# muC.net
KiCad netlist of a schematic drawn in Altium Designer
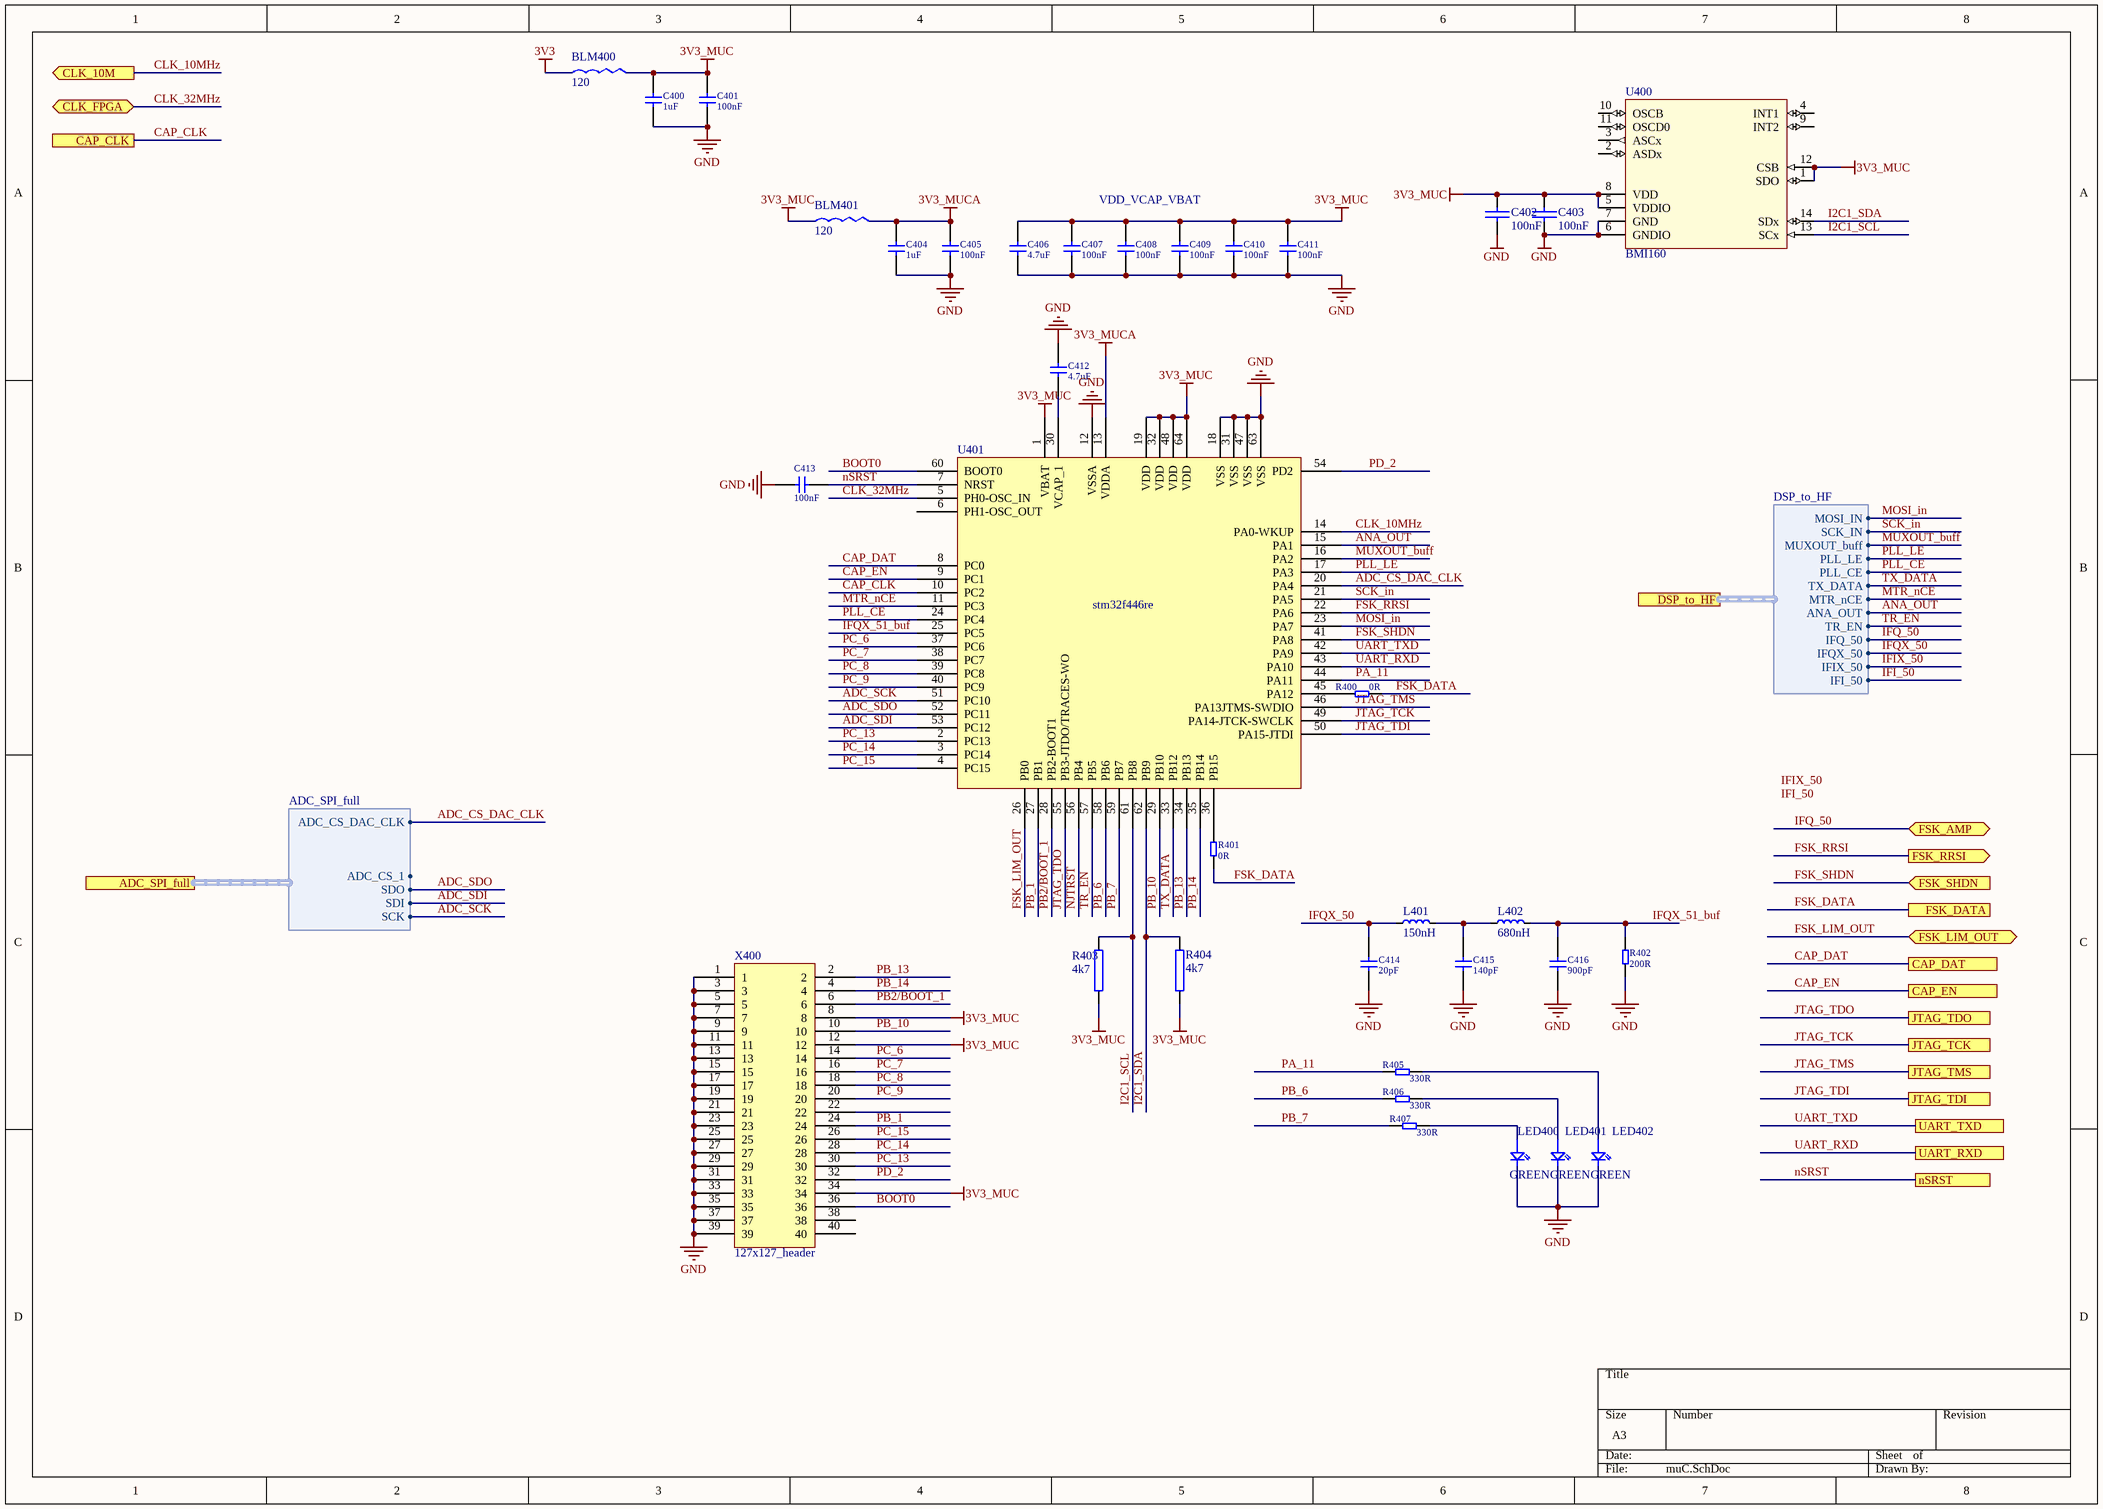
[diagram p0: muC.SchDoc]

(export (version "E")
  (design (tool "Eeschema 10.0.6"))
  (components
    (comp (ref "BLM400")
      (value "FerriteBeat")
      (footprint "BLM18SG121TN1")
      (description "BLM18SG121TN1")
      (fields (field (name "ALTIUM_UNNAMED_1") "120"))
      (libsource (lib "zynq_board") (part "FerriteBeat"))
    )
    (comp (ref "BLM401")
      (value "FerriteBeat")
      (footprint "BLM18SG121TN1")
      (description "BLM18SG121TN1")
      (fields (field (name "ALTIUM_UNNAMED_1") "120"))
      (libsource (lib "zynq_board") (part "FerriteBeat"))
    )
    (comp (ref "C400")
      (value "1uF")
      (footprint "C_SMD_0603")
      (description "1uF, 0603, 6.3V, 10%, X5R")
      (fields (field (name "Comment") "SMD capacitor"))
      (libsource (lib "zynq_board") (part "C_SMD"))
    )
    (comp (ref "C401")
      (value "100nF")
      (footprint "C_SMD_0402")
      (description "100nF, 0402, 6.3V, 10%, X5R")
      (fields (field (name "Comment") "SMD capacitor"))
      (libsource (lib "zynq_board") (part "C_SMD"))
    )
    (comp (ref "C402")
      (value "100nF")
      (footprint "0402RN")
      (description "MLCC, X7R, 16V, 5%, 0402")
      (fields (field (name "PART NUMBER") "100n, 0402, 16V, X7R, 5%"))
      (libsource (lib "Symeo_libs") (part "_CAP"))
    )
    (comp (ref "C403")
      (value "100nF")
      (footprint "0402RN")
      (description "MLCC, X7R, 16V, 5%, 0402")
      (fields (field (name "PART NUMBER") "100n, 0402, 16V, X7R, 5%"))
      (libsource (lib "Symeo_libs") (part "_CAP"))
    )
    (comp (ref "C404")
      (value "1uF")
      (footprint "C_SMD_0603")
      (description "1uF, 0603, 6.3V, 10%, X5R")
      (fields (field (name "Comment") "SMD capacitor"))
      (libsource (lib "zynq_board") (part "C_SMD"))
    )
    (comp (ref "C405")
      (value "100nF")
      (footprint "C_SMD_0402")
      (description "100nF, 0402, 6.3V, 10%, X5R")
      (fields (field (name "Comment") "SMD capacitor"))
      (libsource (lib "zynq_board") (part "C_SMD"))
    )
    (comp (ref "C406")
      (value "4.7uF")
      (footprint "C_SMD_0603")
      (description "4.7uF, 0603, 6.3V, 10%, X5R")
      (fields (field (name "Comment") "SMD capacitor"))
      (libsource (lib "zynq_board") (part "C_SMD"))
    )
    (comp (ref "C407")
      (value "100nF")
      (footprint "C_SMD_0402")
      (description "100nF, 0402, 6.3V, 10%, X5R")
      (fields (field (name "Comment") "SMD capacitor"))
      (libsource (lib "zynq_board") (part "C_SMD"))
    )
    (comp (ref "C408")
      (value "100nF")
      (footprint "C_SMD_0402")
      (description "100nF, 0402, 6.3V, 10%, X5R")
      (fields (field (name "Comment") "SMD capacitor"))
      (libsource (lib "zynq_board") (part "C_SMD"))
    )
    (comp (ref "C409")
      (value "100nF")
      (footprint "C_SMD_0402")
      (description "100nF, 0402, 6.3V, 10%, X5R")
      (fields (field (name "Comment") "SMD capacitor"))
      (libsource (lib "zynq_board") (part "C_SMD"))
    )
    (comp (ref "C410")
      (value "100nF")
      (footprint "C_SMD_0402")
      (description "100nF, 0402, 6.3V, 10%, X5R")
      (fields (field (name "Comment") "SMD capacitor"))
      (libsource (lib "zynq_board") (part "C_SMD"))
    )
    (comp (ref "C411")
      (value "100nF")
      (footprint "C_SMD_0402")
      (description "100nF, 0402, 6.3V, 10%, X5R")
      (fields (field (name "Comment") "SMD capacitor"))
      (libsource (lib "zynq_board") (part "C_SMD"))
    )
    (comp (ref "C412")
      (value "4.7uF")
      (footprint "C_SMD_0603")
      (description "4.7uF, 0603, 6.3V, 10%, X5R")
      (fields (field (name "Comment") "SMD capacitor"))
      (libsource (lib "zynq_board") (part "C_SMD"))
    )
    (comp (ref "C413")
      (value "100nF")
      (footprint "C_SMD_0402")
      (description "100nF, 0402, 6.3V, 10%, X5R")
      (fields (field (name "Comment") "SMD capacitor"))
      (libsource (lib "zynq_board") (part "C_SMD"))
    )
    (comp (ref "C414")
      (value "20pF")
      (footprint "C_SMD_0402")
      (description "20pF, 0402, 6.3V, 10%, X5R")
      (fields (field (name "Comment") "SMD capacitor"))
      (libsource (lib "zynq_board") (part "C_SMD"))
    )
    (comp (ref "C415")
      (value "140pF")
      (footprint "C_SMD_0402")
      (description "140pF, 0402, 6.3V, 10%, X5R")
      (fields (field (name "Comment") "SMD capacitor"))
      (libsource (lib "zynq_board") (part "C_SMD"))
    )
    (comp (ref "C416")
      (value "900pF")
      (footprint "C_SMD_0402")
      (description "900pF, 0402, 6.3V, 10%, X5R")
      (fields (field (name "Comment") "SMD capacitor"))
      (libsource (lib "zynq_board") (part "C_SMD"))
    )
    (comp (ref "L401")
      (value "150nH")
      (footprint "L_0805")
      (description "744761215A,150nH Inductor, Würth Elektorn")
      (libsource (lib "zynq_board") (part "744761215A"))
    )
    (comp (ref "L402")
      (value "680nH")
      (footprint "L_0805")
      (description "744761268A, 680nH")
      (libsource (lib "zynq_board") (part "744761268A"))
    )
    (comp (ref "LED400")
      (value "KPHHS-1005")
      (footprint "R_SMD_0402")
      (fields (field (name "ALTIUM_UNNAMED_1") "GREEN"))
      (libsource (lib "zynq_board") (part "KPHHS-1005"))
    )
    (comp (ref "LED401")
      (value "KPHHS-1005")
      (footprint "R_SMD_0402")
      (fields (field (name "ALTIUM_UNNAMED_1") "GREEN"))
      (libsource (lib "zynq_board") (part "KPHHS-1005"))
    )
    (comp (ref "LED402")
      (value "KPHHS-1005")
      (footprint "R_SMD_0402")
      (fields (field (name "ALTIUM_UNNAMED_1") "GREEN"))
      (libsource (lib "zynq_board") (part "KPHHS-1005"))
    )
    (comp (ref "R400")
      (value "0R")
      (footprint "R_SMD_0402")
      (description "0R,0402")
      (fields (field (name "Comment") "SMD Resistor"))
      (libsource (lib "zynq_board") (part "R_SMD"))
    )
    (comp (ref "R401")
      (value "0R")
      (footprint "R_SMD_0402")
      (description "0R,0402")
      (fields (field (name "Comment") "SMD Resistor"))
      (libsource (lib "zynq_board") (part "R_SMD"))
    )
    (comp (ref "R402")
      (value "200R")
      (footprint "R_SMD_0402")
      (description "200R, 0402, 1%")
      (fields (field (name "Comment") "SMD Resistor"))
      (libsource (lib "zynq_board") (part "R_SMD"))
    )
    (comp (ref "R403")
      (value "4k7")
      (footprint "0402RN")
      (description "1%, 0.063W, 50V, 0402")
      (fields (field (name "PART NUMBER") "4k7, 0402, 1%, 0.063W, 50V"))
      (libsource (lib "Symeo_libs") (part "_RES"))
    )
    (comp (ref "R404")
      (value "4k7")
      (footprint "0402RN")
      (description "1%, 0.063W, 50V, 0402")
      (fields (field (name "PART NUMBER") "4k7, 0402, 1%, 0.063W, 50V"))
      (libsource (lib "Symeo_libs") (part "_RES"))
    )
    (comp (ref "R405")
      (value "330R")
      (footprint "R_SMD_0402")
      (description "330R, 0402, 1%")
      (fields (field (name "Comment") "SMD Resistor"))
      (libsource (lib "zynq_board") (part "R_SMD"))
    )
    (comp (ref "R406")
      (value "330R")
      (footprint "R_SMD_0402")
      (description "330R, 0402, 1%")
      (fields (field (name "Comment") "SMD Resistor"))
      (libsource (lib "zynq_board") (part "R_SMD"))
    )
    (comp (ref "R407")
      (value "330R")
      (footprint "R_SMD_0402")
      (description "330R, 0402, 1%")
      (fields (field (name "Comment") "SMD Resistor"))
      (libsource (lib "zynq_board") (part "R_SMD"))
    )
    (comp (ref "U400")
      (value "BMI160")
      (footprint "BMI160")
      (description "Bosch Accelerometer and Gyro; I2C & SPI")
      (fields (field (name "PART NUMBER") "Sensor BMI160"))
      (libsource (lib "Symeo_libs") (part "BMI160"))
    )
    (comp (ref "U401")
      (value "stm32f446re")
      (footprint "LQFP64")
      (description "32uC")
      (libsource (lib "zynq_board") (part "stm32f446re"))
    )
    (comp (ref "X400")
      (value "127x127_header")
      (footprint "Header_127x127_40PIN")
      (description "127x127_header_throughole, 2x20")
      (libsource (lib "zynq_board") (part "Header_2x20_127mm"))
    )
  )
  (nets
    (net (code "3") (name "/ADC_CS_DAC_CLK") (class "Default")
      (node (ref "U401") (pin "20") (pinfunction "PA4_20") (pintype "passive"))
    )
    (net (code "4") (name "/ADC_SCK") (class "Default")
      (node (ref "U401") (pin "51") (pinfunction "PC10_51") (pintype "passive"))
    )
    (net (code "5") (name "/ADC_SDI") (class "Default")
      (node (ref "U401") (pin "53") (pinfunction "PC12_53") (pintype "passive"))
    )
    (net (code "6") (name "/ADC_SDO") (class "Default")
      (node (ref "U401") (pin "52") (pinfunction "PC11_52") (pintype "passive"))
    )
    (net (code "7") (name "/ANA_OUT") (class "Default")
      (node (ref "U401") (pin "15") (pinfunction "PA1_15") (pintype "passive"))
    )
    (net (code "8") (name "/BOOT0") (class "Default")
      (node (ref "U401") (pin "60") (pinfunction "BOOT0_60") (pintype "passive"))
      (node (ref "X400") (pin "36") (pinfunction "36_36") (pintype "passive"))
    )
    (net (code "9") (name "/CAP_CLK") (class "Default")
      (node (ref "U401") (pin "10") (pinfunction "PC2_10") (pintype "passive"))
    )
    (net (code "10") (name "/CAP_DAT") (class "Default")
      (node (ref "U401") (pin "8") (pinfunction "PC0_8") (pintype "passive"))
    )
    (net (code "11") (name "/CAP_EN") (class "Default")
      (node (ref "U401") (pin "9") (pinfunction "PC1_9") (pintype "passive"))
    )
    (net (code "12") (name "/CLK_10MHz") (class "Default")
      (node (ref "U401") (pin "14") (pinfunction "PA0-WKUP_14") (pintype "passive"))
    )
    (net (code "13") (name "/CLK_32MHz") (class "Default")
      (node (ref "U401") (pin "5") (pinfunction "PH0-OSC_IN_5") (pintype "passive"))
    )
    (net (code "14") (name "/FSK_DATA") (class "Default")
      (node (ref "R400") (pin "1") (pinfunction "1_1") (pintype "passive"))
      (node (ref "R401") (pin "2") (pinfunction "2_2") (pintype "passive"))
    )
    (net (code "15") (name "/FSK_LIM_OUT") (class "Default")
      (node (ref "U401") (pin "26") (pinfunction "PB0_26") (pintype "passive"))
    )
    (net (code "16") (name "/FSK_RRSI") (class "Default")
      (node (ref "U401") (pin "22") (pinfunction "PA6_22") (pintype "passive"))
    )
    (net (code "17") (name "/FSK_SHDN") (class "Default")
      (node (ref "U401") (pin "41") (pinfunction "PA8_41") (pintype "passive"))
    )
    (net (code "18") (name "/I2C1_SCL") (class "Default")
      (node (ref "R403") (pin "2") (pintype "passive"))
      (node (ref "U400") (pin "13") (pinfunction "SCx_13") (pintype "input"))
      (node (ref "U401") (pin "61") (pinfunction "PB8_61") (pintype "passive"))
    )
    (net (code "19") (name "/I2C1_SDA") (class "Default")
      (node (ref "R404") (pin "2") (pintype "passive"))
      (node (ref "U400") (pin "14") (pinfunction "SDx_14") (pintype "bidirectional"))
      (node (ref "U401") (pin "62") (pinfunction "PB9_62") (pintype "passive"))
    )
    (net (code "22") (name "/IFQX_50") (class "Default")
      (node (ref "C414") (pin "1") (pinfunction "1_1") (pintype "passive"))
      (node (ref "L401") (pin "2") (pinfunction "2_2") (pintype "passive"))
    )
    (net (code "23") (name "/IFQX_51_buf") (class "Default")
      (node (ref "C416") (pin "1") (pinfunction "1_1") (pintype "passive"))
      (node (ref "L402") (pin "1") (pinfunction "1_1") (pintype "passive"))
      (node (ref "R402") (pin "1") (pinfunction "1_1") (pintype "passive"))
      (node (ref "U401") (pin "25") (pinfunction "PC5_25") (pintype "passive"))
    )
    (net (code "25") (name "/JTAG_TCK") (class "Default")
      (node (ref "U401") (pin "49") (pinfunction "PA14-JTCK-SWCLK_49") (pintype "passive"))
    )
    (net (code "26") (name "/JTAG_TDI") (class "Default")
      (node (ref "U401") (pin "50") (pinfunction "PA15-JTDI_50") (pintype "passive"))
    )
    (net (code "27") (name "/JTAG_TDO") (class "Default")
      (node (ref "U401") (pin "55") (pinfunction "PB3-JTDO/TRACES-WO_55") (pintype "passive"))
    )
    (net (code "28") (name "/JTAG_TMS") (class "Default")
      (node (ref "U401") (pin "46") (pinfunction "PA13JTMS-SWDIO_46") (pintype "passive"))
    )
    (net (code "29") (name "/MOSI_in") (class "Default")
      (node (ref "U401") (pin "23") (pinfunction "PA7_23") (pintype "passive"))
    )
    (net (code "30") (name "/MTR_nCE") (class "Default")
      (node (ref "U401") (pin "11") (pinfunction "PC3_11") (pintype "passive"))
    )
    (net (code "31") (name "/MUXOUT_buff") (class "Default")
      (node (ref "U401") (pin "16") (pinfunction "PA2_16") (pintype "passive"))
    )
    (net (code "32") (name "/NJTRST") (class "Default")
      (node (ref "U401") (pin "56") (pinfunction "PB4_56") (pintype "passive"))
    )
    (net (code "33") (name "/PA_11") (class "Default")
      (node (ref "R405") (pin "1") (pinfunction "1_1") (pintype "passive"))
      (node (ref "U401") (pin "44") (pinfunction "PA11_44") (pintype "passive"))
    )
    (net (code "34") (name "/PB2{slash}BOOT_1") (class "Default")
      (node (ref "U401") (pin "28") (pinfunction "PB2-BOOT1_28") (pintype "passive"))
      (node (ref "X400") (pin "6") (pinfunction "6_6") (pintype "passive"))
    )
    (net (code "35") (name "/PB_1") (class "Default")
      (node (ref "U401") (pin "27") (pinfunction "PB1_27") (pintype "passive"))
      (node (ref "X400") (pin "24") (pinfunction "24_24") (pintype "passive"))
    )
    (net (code "36") (name "/PB_6") (class "Default")
      (node (ref "R406") (pin "1") (pinfunction "1_1") (pintype "passive"))
      (node (ref "U401") (pin "58") (pinfunction "PB6_58") (pintype "passive"))
    )
    (net (code "37") (name "/PB_7") (class "Default")
      (node (ref "R407") (pin "1") (pinfunction "1_1") (pintype "passive"))
      (node (ref "U401") (pin "59") (pinfunction "PB7_59") (pintype "passive"))
    )
    (net (code "38") (name "/PB_10") (class "Default")
      (node (ref "U401") (pin "29") (pinfunction "PB10_29") (pintype "passive"))
      (node (ref "X400") (pin "10") (pinfunction "10_10") (pintype "passive"))
    )
    (net (code "39") (name "/PB_13") (class "Default")
      (node (ref "U401") (pin "34") (pinfunction "PB13_34") (pintype "passive"))
      (node (ref "X400") (pin "2") (pinfunction "2_2") (pintype "passive"))
    )
    (net (code "40") (name "/PB_14") (class "Default")
      (node (ref "U401") (pin "35") (pinfunction "PB14_35") (pintype "passive"))
      (node (ref "X400") (pin "4") (pinfunction "4_4") (pintype "passive"))
    )
    (net (code "41") (name "/PC_6") (class "Default")
      (node (ref "U401") (pin "37") (pinfunction "PC6_37") (pintype "passive"))
      (node (ref "X400") (pin "14") (pinfunction "14_14") (pintype "passive"))
    )
    (net (code "42") (name "/PC_7") (class "Default")
      (node (ref "U401") (pin "38") (pinfunction "PC7_38") (pintype "passive"))
      (node (ref "X400") (pin "16") (pinfunction "16_16") (pintype "passive"))
    )
    (net (code "43") (name "/PC_8") (class "Default")
      (node (ref "U401") (pin "39") (pinfunction "PC8_39") (pintype "passive"))
      (node (ref "X400") (pin "18") (pinfunction "18_18") (pintype "passive"))
    )
    (net (code "44") (name "/PC_9") (class "Default")
      (node (ref "U401") (pin "40") (pinfunction "PC9_40") (pintype "passive"))
      (node (ref "X400") (pin "20") (pinfunction "20_20") (pintype "passive"))
    )
    (net (code "45") (name "/PC_13") (class "Default")
      (node (ref "U401") (pin "2") (pinfunction "PC13_2") (pintype "passive"))
      (node (ref "X400") (pin "30") (pinfunction "30_30") (pintype "passive"))
    )
    (net (code "46") (name "/PC_14") (class "Default")
      (node (ref "U401") (pin "3") (pinfunction "PC14_3") (pintype "passive"))
      (node (ref "X400") (pin "28") (pinfunction "28_28") (pintype "passive"))
    )
    (net (code "47") (name "/PC_15") (class "Default")
      (node (ref "U401") (pin "4") (pinfunction "PC15_4") (pintype "passive"))
      (node (ref "X400") (pin "26") (pinfunction "26_26") (pintype "passive"))
    )
    (net (code "48") (name "/PD_2") (class "Default")
      (node (ref "U401") (pin "54") (pinfunction "PD2_54") (pintype "passive"))
      (node (ref "X400") (pin "32") (pinfunction "32_32") (pintype "passive"))
    )
    (net (code "49") (name "/PLL_CE") (class "Default")
      (node (ref "U401") (pin "24") (pinfunction "PC4_24") (pintype "passive"))
    )
    (net (code "50") (name "/PLL_LE") (class "Default")
      (node (ref "U401") (pin "17") (pinfunction "PA3_17") (pintype "passive"))
    )
    (net (code "51") (name "/SCK_in") (class "Default")
      (node (ref "U401") (pin "21") (pinfunction "PA5_21") (pintype "passive"))
    )
    (net (code "52") (name "/TR_EN") (class "Default")
      (node (ref "U401") (pin "57") (pinfunction "PB5_57") (pintype "passive"))
    )
    (net (code "53") (name "/TX_DATA") (class "Default")
      (node (ref "U401") (pin "33") (pinfunction "PB12_33") (pintype "passive"))
    )
    (net (code "54") (name "/UART_RXD") (class "Default")
      (node (ref "U401") (pin "43") (pinfunction "PA10_43") (pintype "passive"))
    )
    (net (code "55") (name "/UART_TXD") (class "Default")
      (node (ref "U401") (pin "42") (pinfunction "PA9_42") (pintype "passive"))
    )
    (net (code "56") (name "/nSRST") (class "Default")
      (node (ref "C413") (pin "1") (pinfunction "1_1") (pintype "passive"))
      (node (ref "U401") (pin "7") (pinfunction "NRST_7") (pintype "passive"))
    )
    (net (code "59") (name "3V3") (class "Default")
      (node (ref "BLM400") (pin "1") (pinfunction "1_1") (pintype "passive"))
    )
    (net (code "60") (name "3V3_MUC") (class "Default")
      (node (ref "BLM400") (pin "2") (pinfunction "2_2") (pintype "passive"))
      (node (ref "BLM401") (pin "1") (pinfunction "1_1") (pintype "passive"))
      (node (ref "C400") (pin "1") (pinfunction "1_1") (pintype "passive"))
      (node (ref "C401") (pin "1") (pinfunction "1_1") (pintype "passive"))
      (node (ref "C402") (pin "1") (pintype "passive"))
      (node (ref "C403") (pin "1") (pintype "passive"))
      (node (ref "C406") (pin "1") (pinfunction "1_1") (pintype "passive"))
      (node (ref "C407") (pin "1") (pinfunction "1_1") (pintype "passive"))
      (node (ref "C408") (pin "1") (pinfunction "1_1") (pintype "passive"))
      (node (ref "C409") (pin "1") (pinfunction "1_1") (pintype "passive"))
      (node (ref "C410") (pin "1") (pinfunction "1_1") (pintype "passive"))
      (node (ref "C411") (pin "1") (pinfunction "1_1") (pintype "passive"))
      (node (ref "R403") (pin "1") (pintype "passive"))
      (node (ref "R404") (pin "1") (pintype "passive"))
      (node (ref "U400") (pin "1") (pinfunction "SDO_1") (pintype "bidirectional"))
      (node (ref "U400") (pin "12") (pinfunction "CSB_12") (pintype "input"))
      (node (ref "U400") (pin "5") (pinfunction "VDDIO_5") (pintype "power_in"))
      (node (ref "U400") (pin "8") (pinfunction "VDD_8") (pintype "power_in"))
      (node (ref "U401") (pin "1") (pinfunction "VBAT_1") (pintype "passive"))
      (node (ref "U401") (pin "19") (pinfunction "VDD_19") (pintype "passive"))
      (node (ref "U401") (pin "32") (pinfunction "VDD_32") (pintype "passive"))
      (node (ref "U401") (pin "48") (pinfunction "VDD_48") (pintype "passive"))
      (node (ref "U401") (pin "64") (pinfunction "VDD_64") (pintype "passive"))
      (node (ref "X400") (pin "12") (pinfunction "12_12") (pintype "passive"))
      (node (ref "X400") (pin "34") (pinfunction "34_34") (pintype "passive"))
      (node (ref "X400") (pin "8") (pinfunction "8_8") (pintype "passive"))
    )
    (net (code "61") (name "3V3_MUCA") (class "Default")
      (node (ref "BLM401") (pin "2") (pinfunction "2_2") (pintype "passive"))
      (node (ref "C404") (pin "1") (pinfunction "1_1") (pintype "passive"))
      (node (ref "C405") (pin "1") (pinfunction "1_1") (pintype "passive"))
      (node (ref "U401") (pin "13") (pinfunction "VDDA_13") (pintype "passive"))
    )
    (net (code "62") (name "GND") (class "Default")
      (node (ref "C400") (pin "2") (pinfunction "2_2") (pintype "passive"))
      (node (ref "C401") (pin "2") (pinfunction "2_2") (pintype "passive"))
      (node (ref "C402") (pin "2") (pintype "passive"))
      (node (ref "C403") (pin "2") (pintype "passive"))
      (node (ref "C404") (pin "2") (pinfunction "2_2") (pintype "passive"))
      (node (ref "C405") (pin "2") (pinfunction "2_2") (pintype "passive"))
      (node (ref "C406") (pin "2") (pinfunction "2_2") (pintype "passive"))
      (node (ref "C407") (pin "2") (pinfunction "2_2") (pintype "passive"))
      (node (ref "C408") (pin "2") (pinfunction "2_2") (pintype "passive"))
      (node (ref "C409") (pin "2") (pinfunction "2_2") (pintype "passive"))
      (node (ref "C410") (pin "2") (pinfunction "2_2") (pintype "passive"))
      (node (ref "C411") (pin "2") (pinfunction "2_2") (pintype "passive"))
      (node (ref "C412") (pin "2") (pinfunction "2_2") (pintype "passive"))
      (node (ref "C413") (pin "2") (pinfunction "2_2") (pintype "passive"))
      (node (ref "C414") (pin "2") (pinfunction "2_2") (pintype "passive"))
      (node (ref "C415") (pin "2") (pinfunction "2_2") (pintype "passive"))
      (node (ref "C416") (pin "2") (pinfunction "2_2") (pintype "passive"))
      (node (ref "LED400") (pin "2") (pinfunction "2_2") (pintype "passive"))
      (node (ref "LED401") (pin "2") (pinfunction "2_2") (pintype "passive"))
      (node (ref "LED402") (pin "2") (pinfunction "2_2") (pintype "passive"))
      (node (ref "R402") (pin "2") (pinfunction "2_2") (pintype "passive"))
      (node (ref "U400") (pin "6") (pinfunction "GNDIO_6") (pintype "power_in"))
      (node (ref "U400") (pin "7") (pinfunction "GND_7") (pintype "power_in"))
      (node (ref "U401") (pin "12") (pinfunction "VSSA_12") (pintype "passive"))
      (node (ref "U401") (pin "18") (pinfunction "VSS_18") (pintype "passive"))
      (node (ref "U401") (pin "31") (pinfunction "VSS_31") (pintype "passive"))
      (node (ref "U401") (pin "47") (pinfunction "VSS_47") (pintype "passive"))
      (node (ref "U401") (pin "63") (pinfunction "VSS_63") (pintype "passive"))
      (node (ref "X400") (pin "1") (pinfunction "1_1") (pintype "passive"))
      (node (ref "X400") (pin "11") (pinfunction "11_11") (pintype "passive"))
      (node (ref "X400") (pin "13") (pinfunction "13_13") (pintype "passive"))
      (node (ref "X400") (pin "15") (pinfunction "15_15") (pintype "passive"))
      (node (ref "X400") (pin "17") (pinfunction "17_17") (pintype "passive"))
      (node (ref "X400") (pin "19") (pinfunction "19_19") (pintype "passive"))
      (node (ref "X400") (pin "21") (pinfunction "21_21") (pintype "passive"))
      (node (ref "X400") (pin "23") (pinfunction "23_23") (pintype "passive"))
      (node (ref "X400") (pin "25") (pinfunction "25_25") (pintype "passive"))
      (node (ref "X400") (pin "27") (pinfunction "27_27") (pintype "passive"))
      (node (ref "X400") (pin "29") (pinfunction "29_29") (pintype "passive"))
      (node (ref "X400") (pin "3") (pinfunction "3_3") (pintype "passive"))
      (node (ref "X400") (pin "31") (pinfunction "31_31") (pintype "passive"))
      (node (ref "X400") (pin "33") (pinfunction "33_33") (pintype "passive"))
      (node (ref "X400") (pin "35") (pinfunction "35_35") (pintype "passive"))
      (node (ref "X400") (pin "37") (pinfunction "37_37") (pintype "passive"))
      (node (ref "X400") (pin "39") (pinfunction "39_39") (pintype "passive"))
      (node (ref "X400") (pin "5") (pinfunction "5_5") (pintype "passive"))
      (node (ref "X400") (pin "7") (pinfunction "7_7") (pintype "passive"))
      (node (ref "X400") (pin "9") (pinfunction "9_9") (pintype "passive"))
    )
    (net (code "63") (name "Net-(C415-Pad1)") (class "Default")
      (node (ref "C415") (pin "1") (pinfunction "1_1") (pintype "passive"))
      (node (ref "L401") (pin "1") (pinfunction "1_1") (pintype "passive"))
      (node (ref "L402") (pin "2") (pinfunction "2_2") (pintype "passive"))
    )
    (net (code "64") (name "Net-(LED400-Pad1)") (class "Default")
      (node (ref "LED400") (pin "1") (pinfunction "1_1") (pintype "passive"))
      (node (ref "R407") (pin "2") (pinfunction "2_2") (pintype "passive"))
    )
    (net (code "65") (name "Net-(LED401-Pad1)") (class "Default")
      (node (ref "LED401") (pin "1") (pinfunction "1_1") (pintype "passive"))
      (node (ref "R406") (pin "2") (pinfunction "2_2") (pintype "passive"))
    )
    (net (code "66") (name "Net-(LED402-Pad1)") (class "Default")
      (node (ref "LED402") (pin "1") (pinfunction "1_1") (pintype "passive"))
      (node (ref "R405") (pin "2") (pinfunction "2_2") (pintype "passive"))
    )
    (net (code "67") (name "Net-(U401-PA12)") (class "Default")
      (node (ref "R400") (pin "2") (pinfunction "2_2") (pintype "passive"))
      (node (ref "U401") (pin "45") (pinfunction "PA12_45") (pintype "passive"))
    )
    (net (code "68") (name "Net-(U401-PB15)") (class "Default")
      (node (ref "R401") (pin "1") (pinfunction "1_1") (pintype "passive"))
      (node (ref "U401") (pin "36") (pinfunction "PB15_36") (pintype "passive"))
    )
    (net (code "69") (name "Net-(U401-VCAP_1)") (class "Default")
      (node (ref "C412") (pin "1") (pinfunction "1_1") (pintype "passive"))
      (node (ref "U401") (pin "30") (pinfunction "VCAP_1_30") (pintype "passive"))
    )
    (net (code "70") (name "unconnected-(U400-ASCx-Pad3)") (class "Default")
      (node (ref "U400") (pin "3") (pinfunction "ASCx_3") (pintype "output"))
    )
    (net (code "71") (name "unconnected-(U400-ASDx-Pad2)") (class "Default")
      (node (ref "U400") (pin "2") (pinfunction "ASDx_2") (pintype "bidirectional"))
    )
    (net (code "72") (name "unconnected-(U400-INT1-Pad4)") (class "Default")
      (node (ref "U400") (pin "4") (pinfunction "INT1_4") (pintype "bidirectional"))
    )
    (net (code "73") (name "unconnected-(U400-INT2-Pad9)") (class "Default")
      (node (ref "U400") (pin "9") (pinfunction "INT2_9") (pintype "bidirectional"))
    )
    (net (code "74") (name "unconnected-(U400-OSCB-Pad10)") (class "Default")
      (node (ref "U400") (pin "10") (pinfunction "OSCB_10") (pintype "bidirectional"))
    )
    (net (code "75") (name "unconnected-(U400-OSCD0-Pad11)") (class "Default")
      (node (ref "U400") (pin "11") (pinfunction "OSCD0_11") (pintype "bidirectional"))
    )
    (net (code "76") (name "unconnected-(U401-PH1-OSC_OUT-Pad6)") (class "Default")
      (node (ref "U401") (pin "6") (pinfunction "PH1-OSC_OUT_6") (pintype "passive"))
    )
    (net (code "77") (name "unconnected-(X400-Pad22)") (class "Default")
      (node (ref "X400") (pin "22") (pinfunction "22_22") (pintype "passive"))
    )
    (net (code "78") (name "unconnected-(X400-Pad38)") (class "Default")
      (node (ref "X400") (pin "38") (pinfunction "38_38") (pintype "passive"))
    )
    (net (code "79") (name "unconnected-(X400-Pad40)") (class "Default")
      (node (ref "X400") (pin "40") (pinfunction "40_40") (pintype "passive"))
    )
  )
)
